# 3_main_a.net
KiCad netlist of a schematic drawn in EAGLE
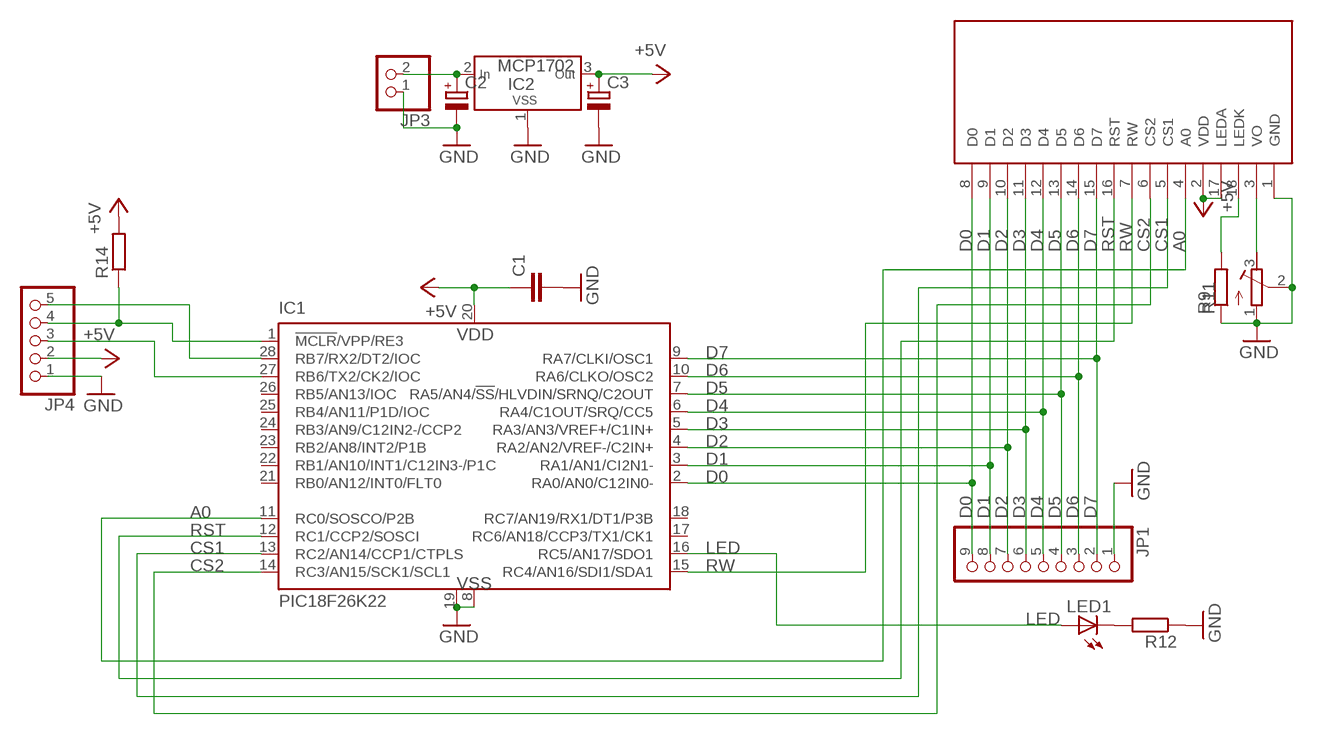
[diagram p0: schematic, sheet 1]

(export (version "E")
  (design (tool "Eeschema 10.0.6"))
  (components
    (comp (ref "C1")
      (value "C-EU025-025X050")
      (footprint "eagle-import:C025-025X050")
      (libsource (lib "eagle-import") (part "C-EU025-025X050"))
    )
    (comp (ref "C2")
      (value "CPOL-EUE2-4")
      (footprint "eagle-import:E2-4")
      (libsource (lib "eagle-import") (part "CPOL-EUE2-4"))
    )
    (comp (ref "C3")
      (value "CPOL-EUE2-4")
      (footprint "eagle-import:E2-4")
      (libsource (lib "eagle-import") (part "CPOL-EUE2-4"))
    )
    (comp (ref "IC1")
      (value "PIC18F26K22")
      (footprint "eagle-import:DIL28-3")
      (libsource (lib "eagle-import") (part "PIC18F26K22"))
    )
    (comp (ref "IC2")
      (value "MCP1702")
      (footprint "eagle-import:TO-92")
      (libsource (lib "eagle-import") (part "MCP1702"))
    )
    (comp (ref "JP1")
      (value "PINHD-1X09_2.54-90°")
      (footprint "eagle-import:1X09_90")
      (libsource (lib "eagle-import") (part "PINHD-1X09_2.54-90°"))
    )
    (comp (ref "JP3")
      (value "PINHD-1X2")
      (footprint "eagle-import:1X02")
      (libsource (lib "eagle-import") (part "PINHD-1X2"))
    )
    (comp (ref "JP4")
      (value "PINHD-1X05_2.54-90°")
      (footprint "eagle-import:1X05_90")
      (libsource (lib "eagle-import") (part "PINHD-1X05_2.54-90°"))
    )
    (comp (ref "LCD1")
      (value "DEM122032")
      (footprint "eagle-import:DEM122032")
      (libsource (lib "eagle-import") (part "DEM122032"))
    )
    (comp (ref "LED1")
      (value "LED3MM")
      (footprint "eagle-import:LED3MM")
      (libsource (lib "eagle-import") (part "LED3MM"))
    )
    (comp (ref "R9")
      (value "R_0207")
      (footprint "eagle-import:R_0207_BIGPADS")
      (libsource (lib "eagle-import") (part "R_0207"))
    )
    (comp (ref "R11")
      (value "R-TRIMM3339P")
      (footprint "eagle-import:RTRIM3339P")
      (libsource (lib "eagle-import") (part "R-TRIMM3339P"))
    )
    (comp (ref "R12")
      (value "R_0207")
      (footprint "eagle-import:R_0207_BIGPADS")
      (libsource (lib "eagle-import") (part "R_0207"))
    )
    (comp (ref "R14")
      (value "R_0207")
      (footprint "eagle-import:R_0207_BIGPADS")
      (libsource (lib "eagle-import") (part "R_0207"))
    )
  )
  (nets
    (net (code "1") (name "+5V") (class "Default")
      (node (ref "C1") (pin "1") (pinfunction "1_1") (pintype "passive"))
      (node (ref "C3") (pin "+") (pinfunction "+_+") (pintype "passive"))
      (node (ref "IC1") (pin "20") (pinfunction "VDD_20") (pintype "power_in"))
      (node (ref "IC2") (pin "3") (pinfunction "OUT_3") (pintype "output"))
      (node (ref "JP4") (pin "2") (pinfunction "2_2") (pintype "passive"))
      (node (ref "LCD1") (pin "17") (pinfunction "LEDA_17") (pintype "bidirectional"))
      (node (ref "LCD1") (pin "2") (pinfunction "VDD_2") (pintype "bidirectional"))
      (node (ref "R14") (pin "P$2") (pinfunction "2_P$2") (pintype "passive"))
    )
    (net (code "2") (name "/A0") (class "Default")
      (node (ref "IC1") (pin "11") (pinfunction "RC0/SOSCO/P2B_11") (pintype "bidirectional"))
      (node (ref "LCD1") (pin "4") (pinfunction "A0_4") (pintype "bidirectional"))
    )
    (net (code "3") (name "/CS1") (class "Default")
      (node (ref "IC1") (pin "13") (pinfunction "RC2/AN14/CCP1/CTPLS_13") (pintype "bidirectional"))
      (node (ref "LCD1") (pin "5") (pinfunction "CS1_5") (pintype "bidirectional"))
    )
    (net (code "4") (name "/CS2") (class "Default")
      (node (ref "IC1") (pin "14") (pinfunction "RC3/AN15/SCK1/SCL1_14") (pintype "bidirectional"))
      (node (ref "LCD1") (pin "6") (pinfunction "CS2_6") (pintype "bidirectional"))
    )
    (net (code "5") (name "/D0") (class "Default")
      (node (ref "IC1") (pin "2") (pinfunction "RA0/AN0/C12IN0-_2") (pintype "bidirectional"))
      (node (ref "JP1") (pin "9") (pinfunction "9_9") (pintype "passive"))
      (node (ref "LCD1") (pin "8") (pinfunction "D0_8") (pintype "bidirectional"))
    )
    (net (code "6") (name "/D1") (class "Default")
      (node (ref "IC1") (pin "3") (pinfunction "RA1/AN1/CI2N1-_3") (pintype "bidirectional"))
      (node (ref "JP1") (pin "8") (pinfunction "8_8") (pintype "passive"))
      (node (ref "LCD1") (pin "9") (pinfunction "D1_9") (pintype "bidirectional"))
    )
    (net (code "7") (name "/D2") (class "Default")
      (node (ref "IC1") (pin "4") (pinfunction "RA2/AN2/VREF-/C2IN+_4") (pintype "bidirectional"))
      (node (ref "JP1") (pin "7") (pinfunction "7_7") (pintype "passive"))
      (node (ref "LCD1") (pin "10") (pinfunction "D2_10") (pintype "bidirectional"))
    )
    (net (code "8") (name "/D3") (class "Default")
      (node (ref "IC1") (pin "5") (pinfunction "RA3/AN3/VREF+/C1IN+_5") (pintype "bidirectional"))
      (node (ref "JP1") (pin "6") (pinfunction "6_6") (pintype "passive"))
      (node (ref "LCD1") (pin "11") (pinfunction "D3_11") (pintype "bidirectional"))
    )
    (net (code "9") (name "/D4") (class "Default")
      (node (ref "IC1") (pin "6") (pinfunction "RA4/C1OUT/SRQ/CC5_6") (pintype "bidirectional"))
      (node (ref "JP1") (pin "5") (pinfunction "5_5") (pintype "passive"))
      (node (ref "LCD1") (pin "12") (pinfunction "D4_12") (pintype "bidirectional"))
    )
    (net (code "10") (name "/D5") (class "Default")
      (node (ref "IC1") (pin "7") (pinfunction "RA5/AN4/~{SS}/HLVDIN/SRNQ/C2OUT_7") (pintype "bidirectional"))
      (node (ref "JP1") (pin "4") (pinfunction "4_4") (pintype "passive"))
      (node (ref "LCD1") (pin "13") (pinfunction "D5_13") (pintype "bidirectional"))
    )
    (net (code "11") (name "/D6") (class "Default")
      (node (ref "IC1") (pin "10") (pinfunction "RA6/CLKO/OSC2_10") (pintype "output"))
      (node (ref "JP1") (pin "3") (pinfunction "3_3") (pintype "passive"))
      (node (ref "LCD1") (pin "14") (pinfunction "D6_14") (pintype "bidirectional"))
    )
    (net (code "12") (name "/D7") (class "Default")
      (node (ref "IC1") (pin "9") (pinfunction "RA7/CLKI/OSC1_9") (pintype "input"))
      (node (ref "JP1") (pin "2") (pinfunction "2_2") (pintype "passive"))
      (node (ref "LCD1") (pin "15") (pinfunction "D7_15") (pintype "bidirectional"))
    )
    (net (code "13") (name "/LED") (class "Default")
      (node (ref "IC1") (pin "16") (pinfunction "RC5/AN17/SDO1_16") (pintype "bidirectional"))
      (node (ref "LED1") (pin "A") (pinfunction "A_A") (pintype "passive"))
    )
    (net (code "14") (name "/RST") (class "Default")
      (node (ref "IC1") (pin "12") (pinfunction "RC1/CCP2/SOSCI_12") (pintype "bidirectional"))
      (node (ref "LCD1") (pin "16") (pinfunction "RST_16") (pintype "bidirectional"))
    )
    (net (code "15") (name "/RW") (class "Default")
      (node (ref "IC1") (pin "15") (pinfunction "RC4/AN16/SDI1/SDA1_15") (pintype "bidirectional"))
      (node (ref "LCD1") (pin "7") (pinfunction "RW_7") (pintype "bidirectional"))
    )
    (net (code "16") (name "GND") (class "Default")
      (node (ref "C1") (pin "2") (pinfunction "2_2") (pintype "passive"))
      (node (ref "C2") (pin "-") (pinfunction "-_-") (pintype "passive"))
      (node (ref "C3") (pin "-") (pinfunction "-_-") (pintype "passive"))
      (node (ref "IC1") (pin "19") (pinfunction "VSS_19") (pintype "power_in"))
      (node (ref "IC1") (pin "8") (pinfunction "VSS_8") (pintype "power_in"))
      (node (ref "IC2") (pin "1") (pinfunction "VSS_1") (pintype "input"))
      (node (ref "JP1") (pin "1") (pinfunction "1_1") (pintype "passive"))
      (node (ref "JP3") (pin "1") (pinfunction "1_1") (pintype "passive"))
      (node (ref "JP4") (pin "1") (pinfunction "1_1") (pintype "passive"))
      (node (ref "LCD1") (pin "1") (pinfunction "GND_1") (pintype "bidirectional"))
      (node (ref "R11") (pin "1") (pinfunction "E_1") (pintype "passive"))
      (node (ref "R11") (pin "2") (pinfunction "S_2") (pintype "passive"))
      (node (ref "R12") (pin "P$1") (pinfunction "1_P$1") (pintype "passive"))
      (node (ref "R9") (pin "P$1") (pinfunction "1_P$1") (pintype "passive"))
    )
    (net (code "17") (name "Net-(IC1-RB6{slash}TX2{slash}CK2{slash}IOC)") (class "Default")
      (node (ref "IC1") (pin "27") (pinfunction "RB6/TX2/CK2/IOC_27") (pintype "bidirectional"))
      (node (ref "JP4") (pin "3") (pinfunction "3_3") (pintype "passive"))
    )
    (net (code "18") (name "Net-(IC1-RB7{slash}RX2{slash}DT2{slash}IOC)") (class "Default")
      (node (ref "IC1") (pin "28") (pinfunction "RB7/RX2/DT2/IOC_28") (pintype "bidirectional"))
      (node (ref "JP4") (pin "5") (pinfunction "5_5") (pintype "passive"))
    )
    (net (code "19") (name "Net-(IC1-~{MCLR}{slash}VPP{slash}RE3)") (class "Default")
      (node (ref "IC1") (pin "1") (pinfunction "~{MCLR}/VPP/RE3_1") (pintype "input"))
      (node (ref "JP4") (pin "4") (pinfunction "4_4") (pintype "passive"))
      (node (ref "R14") (pin "P$1") (pinfunction "1_P$1") (pintype "passive"))
    )
    (net (code "20") (name "Net-(IC2-IN)") (class "Default")
      (node (ref "C2") (pin "+") (pinfunction "+_+") (pintype "passive"))
      (node (ref "IC2") (pin "2") (pinfunction "IN_2") (pintype "input"))
      (node (ref "JP3") (pin "2") (pinfunction "2_2") (pintype "passive"))
    )
    (net (code "21") (name "Net-(LCD1-LEDK)") (class "Default")
      (node (ref "LCD1") (pin "18") (pinfunction "LEDK_18") (pintype "bidirectional"))
      (node (ref "R9") (pin "P$2") (pinfunction "2_P$2") (pintype "passive"))
    )
    (net (code "22") (name "Net-(LCD1-VO)") (class "Default")
      (node (ref "LCD1") (pin "3") (pinfunction "VO_3") (pintype "bidirectional"))
      (node (ref "R11") (pin "3") (pinfunction "A_3") (pintype "passive"))
    )
    (net (code "23") (name "Net-(LED1-C)") (class "Default")
      (node (ref "LED1") (pin "K") (pinfunction "C_K") (pintype "passive"))
      (node (ref "R12") (pin "P$2") (pinfunction "2_P$2") (pintype "passive"))
    )
    (net (code "24") (name "unconnected-(IC1-RB0{slash}AN12{slash}INT0{slash}FLT0-Pad21)") (class "Default")
      (node (ref "IC1") (pin "21") (pinfunction "RB0/AN12/INT0/FLT0_21") (pintype "bidirectional"))
    )
    (net (code "25") (name "unconnected-(IC1-RB1{slash}AN10{slash}INT1{slash}C12IN3-{slash}P1C-Pad22)") (class "Default")
      (node (ref "IC1") (pin "22") (pinfunction "RB1/AN10/INT1/C12IN3-/P1C_22") (pintype "bidirectional"))
    )
    (net (code "26") (name "unconnected-(IC1-RB2{slash}AN8{slash}INT2{slash}P1B-Pad23)") (class "Default")
      (node (ref "IC1") (pin "23") (pinfunction "RB2/AN8/INT2/P1B_23") (pintype "bidirectional"))
    )
    (net (code "27") (name "unconnected-(IC1-RB3{slash}AN9{slash}C12IN2-{slash}CCP2-Pad24)") (class "Default")
      (node (ref "IC1") (pin "24") (pinfunction "RB3/AN9/C12IN2-/CCP2_24") (pintype "bidirectional"))
    )
    (net (code "28") (name "unconnected-(IC1-RB4{slash}AN11{slash}P1D{slash}IOC-Pad25)") (class "Default")
      (node (ref "IC1") (pin "25") (pinfunction "RB4/AN11/P1D/IOC_25") (pintype "bidirectional"))
    )
    (net (code "29") (name "unconnected-(IC1-RB5{slash}AN13{slash}IOC-Pad26)") (class "Default")
      (node (ref "IC1") (pin "26") (pinfunction "RB5/AN13/IOC_26") (pintype "bidirectional"))
    )
    (net (code "30") (name "unconnected-(IC1-RC6{slash}AN18{slash}CCP3{slash}TX1{slash}CK1-Pad17)") (class "Default")
      (node (ref "IC1") (pin "17") (pinfunction "RC6/AN18/CCP3/TX1/CK1_17") (pintype "bidirectional"))
    )
    (net (code "31") (name "unconnected-(IC1-RC7{slash}AN19{slash}RX1{slash}DT1{slash}P3B-Pad18)") (class "Default")
      (node (ref "IC1") (pin "18") (pinfunction "RC7/AN19/RX1/DT1/P3B_18") (pintype "bidirectional"))
    )
  )
)
